# v4_2.net
KiCad netlist of a schematic drawn in EasyEDA
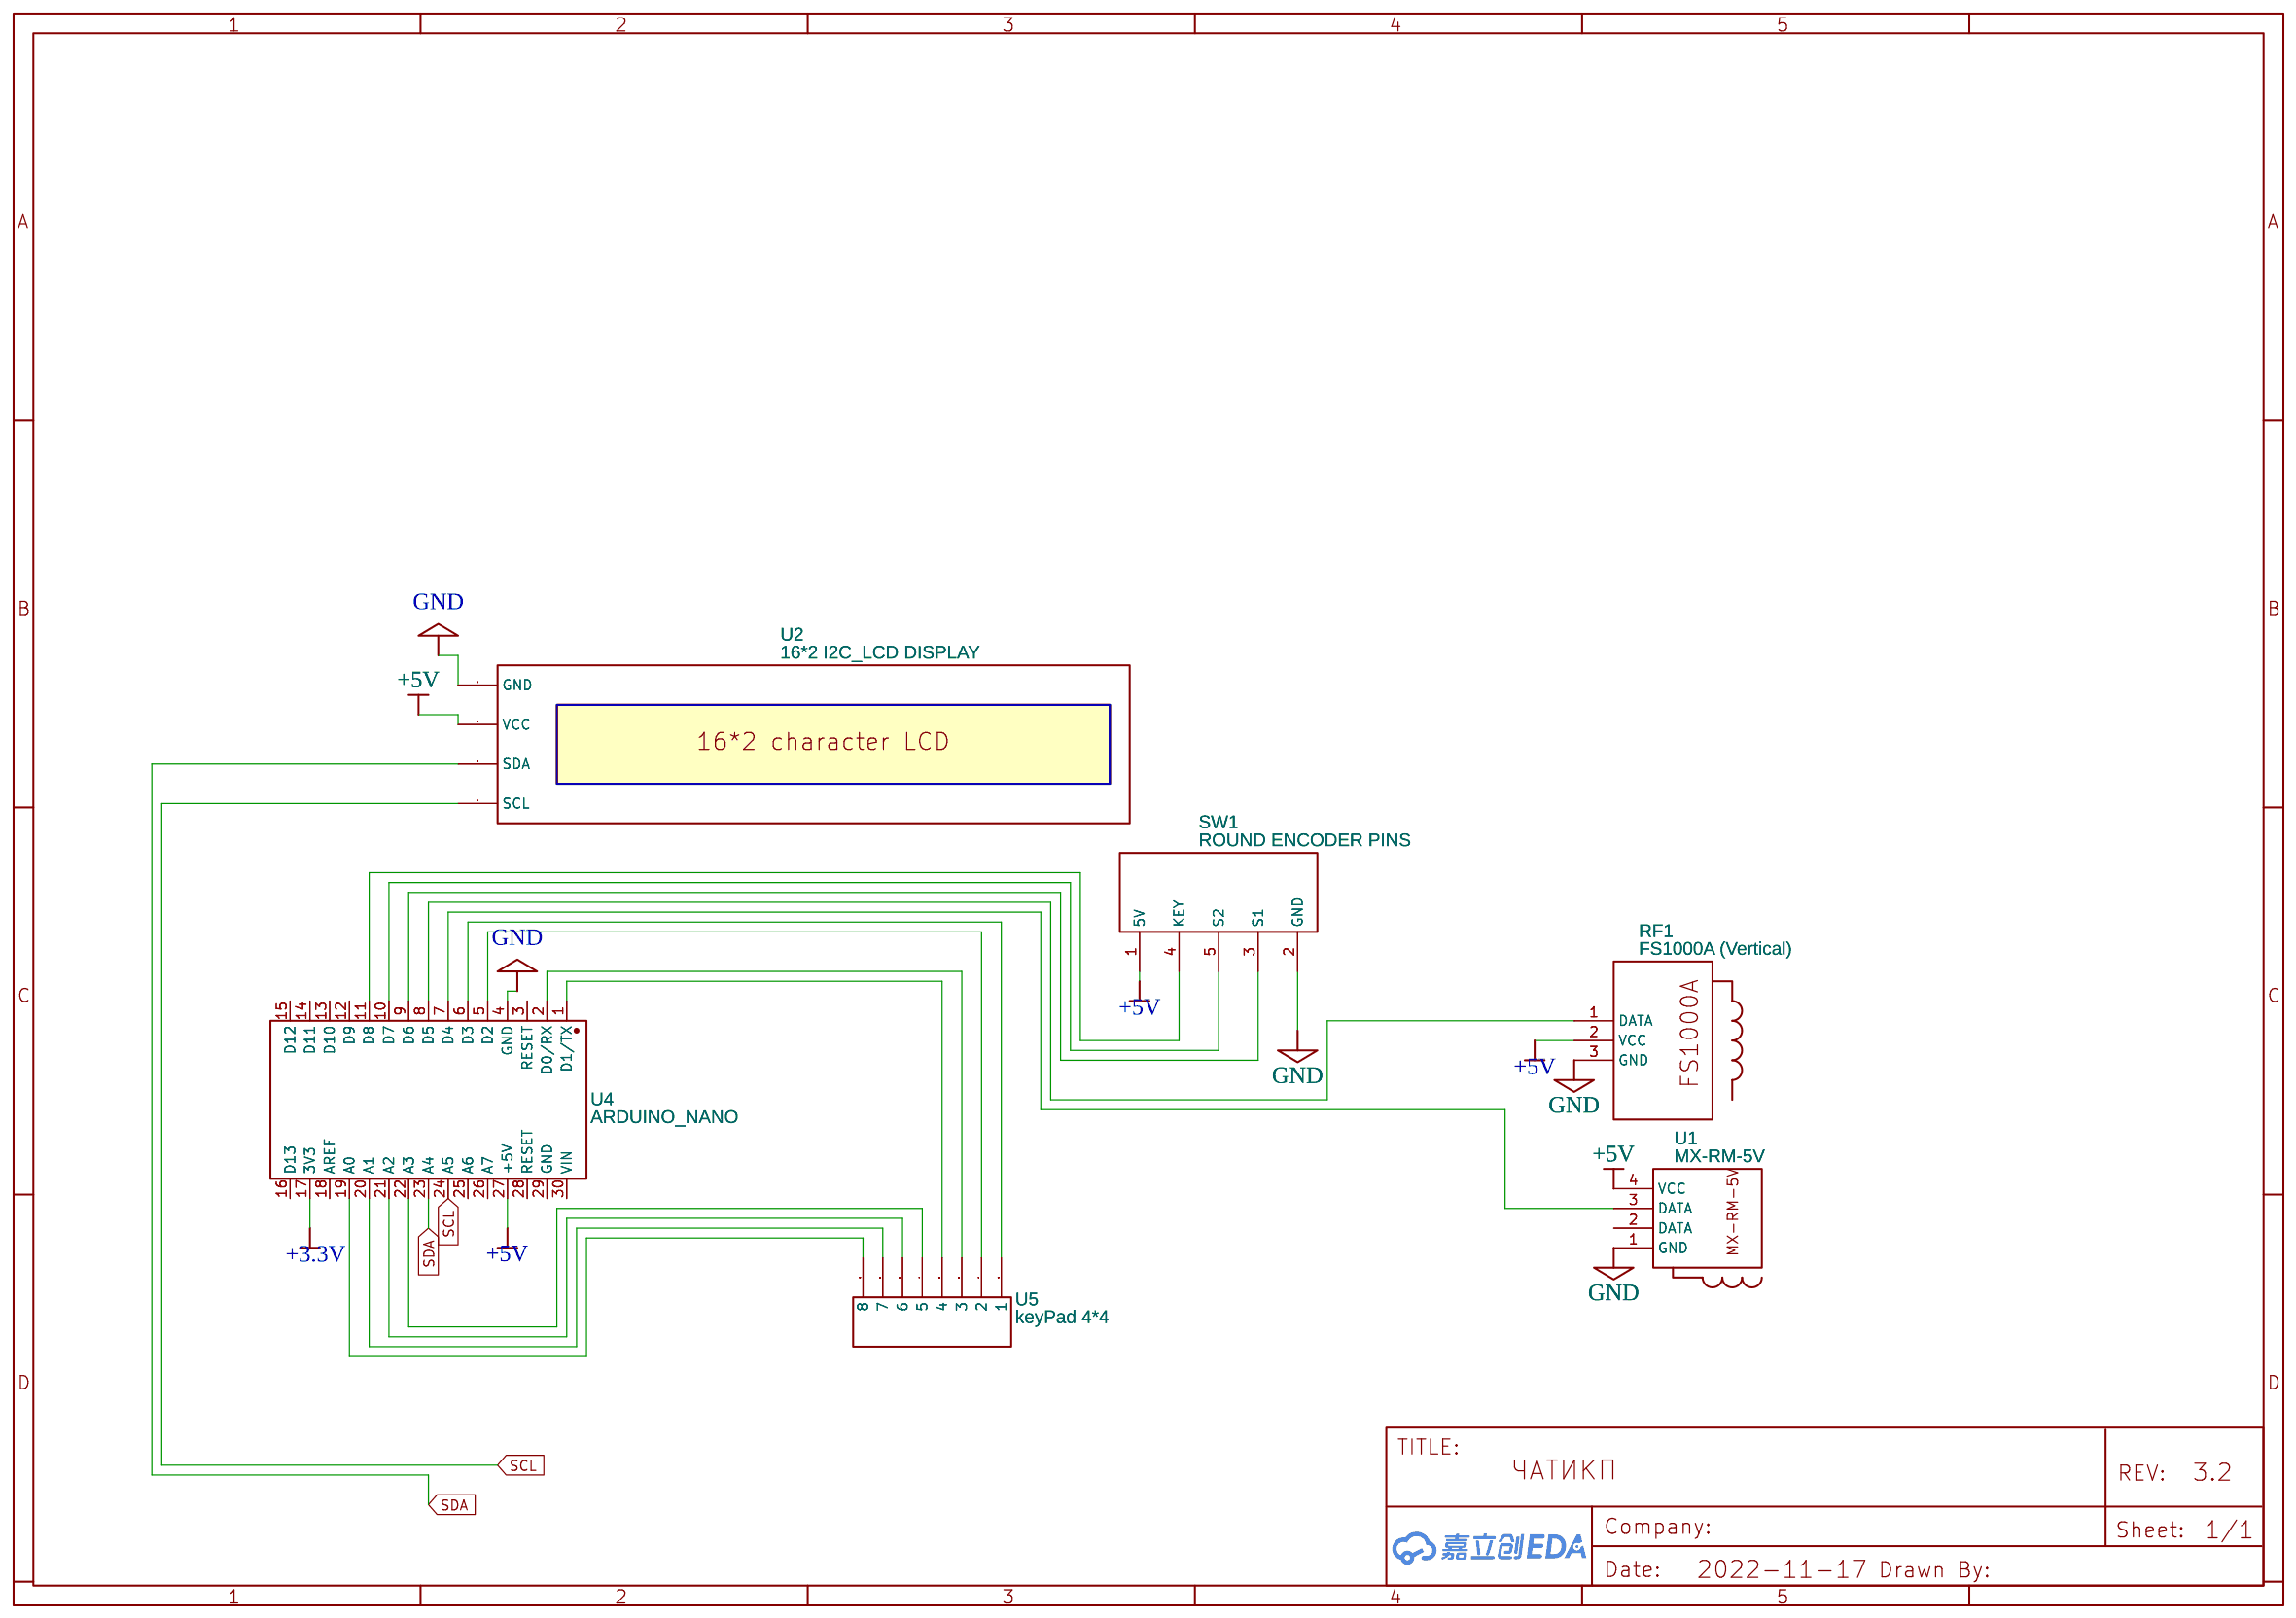
[diagram p0: schematic sheet]

(export (version "E")
  (design (tool "Eeschema 10.0.6"))
  (components
    (comp (ref "RF1") (value "FS1000A (Vertical)") (libsource (lib "") (part "FS1000A (Vertical)")))
    (comp (ref "SW1")
      (value "ROUND ENCODER PINS")
      (fields
        (field (name "BOM_Manufacturer Part") "PEC11R-4015F-S0024")
        (field (name "BOM_Supplier Part") "C143789")
      )
      (libsource (lib "") (part "ROUND ENCODER PINS"))
    )
    (comp (ref "U1") (value "MX-RM-5V") (libsource (lib "") (part "MX-RM-5V")))
    (comp (ref "U2")
      (value "16*2 I2C_LCD DISPLAY")
      (fields (field (name "BOM_Supplier Part") "undefined"))
      (libsource (lib "") (part "16*2 I2C_LCD DISPLAY"))
    )
    (comp (ref "U4")
      (value "ARDUINO_NANO")
      (fields (field (name "BOM_Supplier Part") "C9900017879"))
      (libsource (lib "") (part "ARDUINO_NANO"))
    )
    (comp (ref "U5") (value "keyPad 4*4") (libsource (lib "") (part "keyPad 4*4")))
  )
  (nets
    (net (code "1") (name "+3.3V") (class "Default")
      (node (ref "U4") (pin "17") (pinfunction "3V3_17") (pintype "unspecified"))
    )
    (net (code "2") (name "+5V") (class "Default")
      (node (ref "RF1") (pin "2") (pinfunction "VCC_2") (pintype "unspecified"))
      (node (ref "SW1") (pin "1") (pinfunction "5V_1") (pintype "unspecified"))
      (node (ref "U1") (pin "4") (pinfunction "VCC_4") (pintype "unspecified"))
      (node (ref "U2") (pin "2") (pinfunction "VCC_2") (pintype "unspecified"))
      (node (ref "U4") (pin "27") (pinfunction "+5V_27") (pintype "unspecified"))
    )
    (net (code "3") (name "GND") (class "Default")
      (node (ref "RF1") (pin "3") (pinfunction "GND_3") (pintype "unspecified"))
      (node (ref "SW1") (pin "2") (pinfunction "GND_2") (pintype "unspecified"))
      (node (ref "U1") (pin "1") (pinfunction "GND_1") (pintype "unspecified"))
      (node (ref "U2") (pin "1") (pinfunction "GND_1") (pintype "unspecified"))
      (node (ref "U4") (pin "4") (pinfunction "GND_4") (pintype "unspecified"))
    )
    (net (code "4") (name "Net-(RF1-DATA)") (class "Default")
      (node (ref "RF1") (pin "1") (pinfunction "DATA_1") (pintype "unspecified"))
      (node (ref "U4") (pin "8") (pinfunction "D5_8") (pintype "unspecified"))
    )
    (net (code "5") (name "Net-(SW1-KEY)") (class "Default")
      (node (ref "SW1") (pin "4") (pinfunction "KEY_4") (pintype "unspecified"))
      (node (ref "U4") (pin "11") (pinfunction "D8_11") (pintype "unspecified"))
    )
    (net (code "6") (name "Net-(SW1-S1)") (class "Default")
      (node (ref "SW1") (pin "3") (pinfunction "S1_3") (pintype "unspecified"))
      (node (ref "U4") (pin "9") (pinfunction "D6_9") (pintype "unspecified"))
    )
    (net (code "7") (name "Net-(SW1-S2)") (class "Default")
      (node (ref "SW1") (pin "5") (pinfunction "S2_5") (pintype "unspecified"))
      (node (ref "U4") (pin "10") (pinfunction "D7_10") (pintype "unspecified"))
    )
    (net (code "8") (name "Net-(U4-A0)") (class "Default")
      (node (ref "U4") (pin "19") (pinfunction "A0_19") (pintype "unspecified"))
      (node (ref "U5") (pin "10") (pinfunction "8_10") (pintype "unspecified"))
    )
    (net (code "9") (name "Net-(U4-A1)") (class "Default")
      (node (ref "U4") (pin "20") (pinfunction "A1_20") (pintype "unspecified"))
      (node (ref "U5") (pin "9") (pinfunction "7_9") (pintype "unspecified"))
    )
    (net (code "10") (name "Net-(U4-A2)") (class "Default")
      (node (ref "U4") (pin "21") (pinfunction "A2_21") (pintype "unspecified"))
      (node (ref "U5") (pin "8") (pinfunction "6_8") (pintype "unspecified"))
    )
    (net (code "11") (name "Net-(U4-A3)") (class "Default")
      (node (ref "U4") (pin "22") (pinfunction "A3_22") (pintype "unspecified"))
      (node (ref "U5") (pin "7") (pinfunction "5_7") (pintype "unspecified"))
    )
    (net (code "12") (name "Net-(U4-D0{slash}RX)") (class "Default")
      (node (ref "U4") (pin "2") (pinfunction "D0/RX_2") (pintype "unspecified"))
      (node (ref "U5") (pin "5") (pinfunction "3_5") (pintype "unspecified"))
    )
    (net (code "13") (name "Net-(U4-D1{slash}TX)") (class "Default")
      (node (ref "U4") (pin "1") (pinfunction "D1/TX_1") (pintype "unspecified"))
      (node (ref "U5") (pin "6") (pinfunction "4_6") (pintype "unspecified"))
    )
    (net (code "14") (name "Net-(U4-D2)") (class "Default")
      (node (ref "U4") (pin "5") (pinfunction "D2_5") (pintype "unspecified"))
      (node (ref "U5") (pin "4") (pinfunction "2_4") (pintype "unspecified"))
    )
    (net (code "15") (name "Net-(U4-D3)") (class "Default")
      (node (ref "U4") (pin "6") (pinfunction "D3_6") (pintype "unspecified"))
      (node (ref "U5") (pin "3") (pinfunction "1_3") (pintype "unspecified"))
    )
    (net (code "16") (name "Net-(U4-D4)") (class "Default")
      (node (ref "U1") (pin "3") (pinfunction "DATA_3") (pintype "unspecified"))
      (node (ref "U4") (pin "7") (pinfunction "D4_7") (pintype "unspecified"))
    )
    (net (code "17") (name "SCL") (class "Default")
      (node (ref "U2") (pin "4") (pinfunction "SCL_4") (pintype "unspecified"))
      (node (ref "U4") (pin "24") (pinfunction "A5_24") (pintype "unspecified"))
    )
    (net (code "18") (name "SDA") (class "Default")
      (node (ref "U2") (pin "3") (pinfunction "SDA_3") (pintype "unspecified"))
      (node (ref "U4") (pin "23") (pinfunction "A4_23") (pintype "unspecified"))
    )
    (net (code "19") (name "unconnected-(U1-DATA-Pad2)") (class "Default")
      (node (ref "U1") (pin "2") (pinfunction "DATA_2") (pintype "unspecified"))
    )
    (net (code "20") (name "unconnected-(U4-A6-Pad25)") (class "Default")
      (node (ref "U4") (pin "25") (pinfunction "A6_25") (pintype "unspecified"))
    )
    (net (code "21") (name "unconnected-(U4-A7-Pad26)") (class "Default")
      (node (ref "U4") (pin "26") (pinfunction "A7_26") (pintype "unspecified"))
    )
    (net (code "22") (name "unconnected-(U4-AREF-Pad18)") (class "Default")
      (node (ref "U4") (pin "18") (pinfunction "AREF_18") (pintype "unspecified"))
    )
    (net (code "23") (name "unconnected-(U4-D9-Pad12)") (class "Default")
      (node (ref "U4") (pin "12") (pinfunction "D9_12") (pintype "unspecified"))
    )
    (net (code "24") (name "unconnected-(U4-D10-Pad13)") (class "Default")
      (node (ref "U4") (pin "13") (pinfunction "D10_13") (pintype "unspecified"))
    )
    (net (code "25") (name "unconnected-(U4-D11-Pad14)") (class "Default")
      (node (ref "U4") (pin "14") (pinfunction "D11_14") (pintype "unspecified"))
    )
    (net (code "26") (name "unconnected-(U4-D12-Pad15)") (class "Default")
      (node (ref "U4") (pin "15") (pinfunction "D12_15") (pintype "unspecified"))
    )
    (net (code "27") (name "unconnected-(U4-D13-Pad16)") (class "Default")
      (node (ref "U4") (pin "16") (pinfunction "D13_16") (pintype "unspecified"))
    )
    (net (code "28") (name "unconnected-(U4-GND-Pad29)") (class "Default")
      (node (ref "U4") (pin "29") (pinfunction "GND_29") (pintype "unspecified"))
    )
    (net (code "29") (name "unconnected-(U4-RESET-Pad3)") (class "Default")
      (node (ref "U4") (pin "3") (pinfunction "RESET_3") (pintype "unspecified"))
    )
    (net (code "30") (name "unconnected-(U4-RESET-Pad28)") (class "Default")
      (node (ref "U4") (pin "28") (pinfunction "RESET_28") (pintype "unspecified"))
    )
    (net (code "31") (name "unconnected-(U4-VIN-Pad30)") (class "Default")
      (node (ref "U4") (pin "30") (pinfunction "VIN_30") (pintype "unspecified"))
    )
  )
)
